# BigLatchingRelayOnAStick.net
KiCad netlist of a schematic drawn in EAGLE
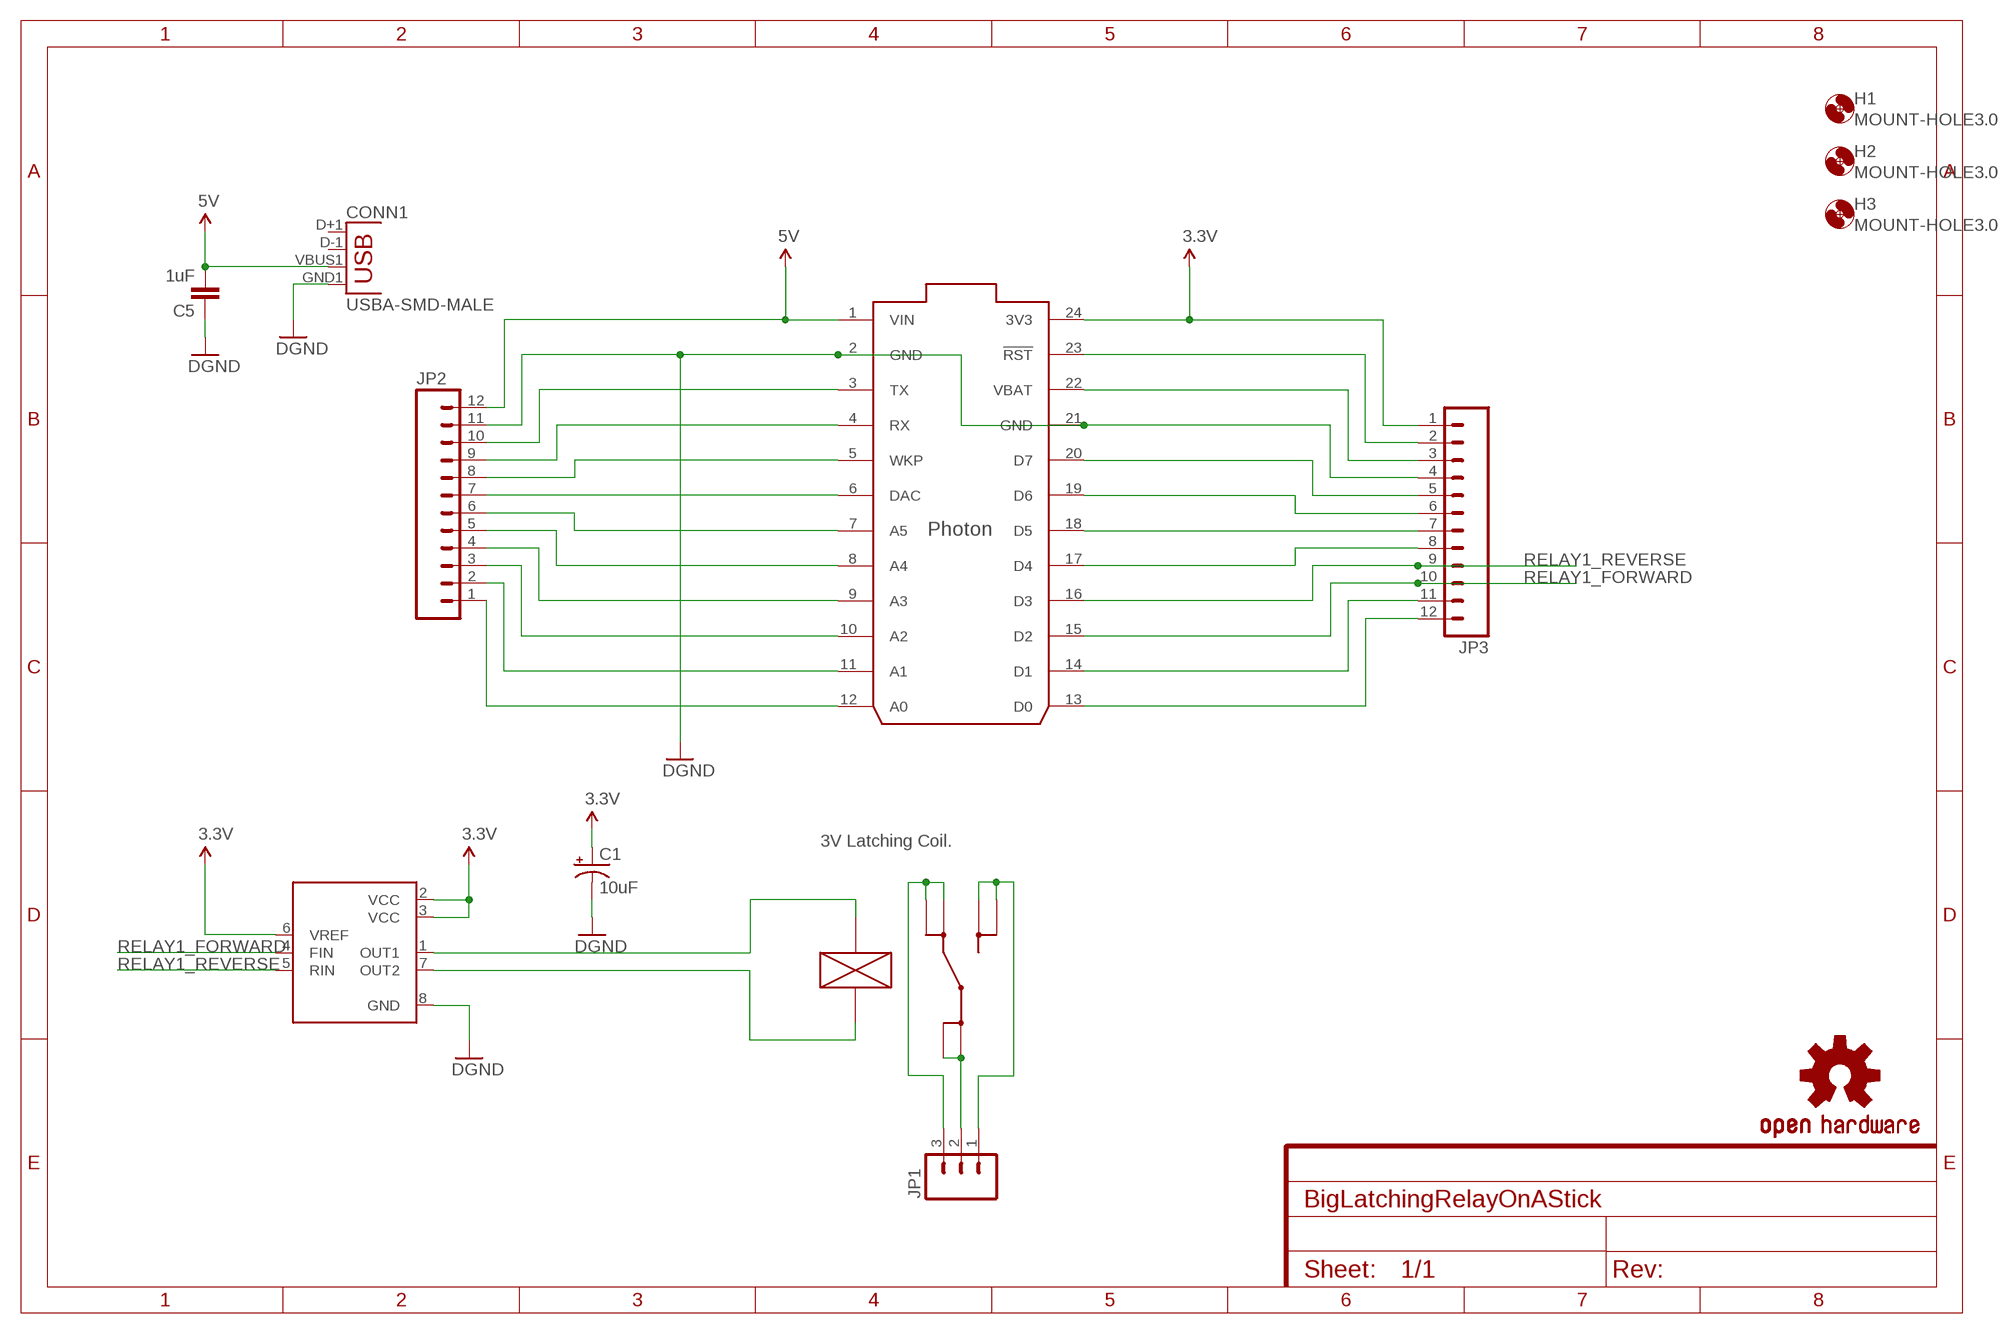
[diagram p0: schematic, sheet 1]

(export (version "E")
  (design (tool "Eeschema 10.0.6"))
  (components
    (comp (ref "C1")
      (value "10uF")
      (footprint "eagle-import:EIA3216")
      (libsource (lib "eagle-import") (part "10UF-16V-10%(TANT)"))
    )
    (comp (ref "C5")
      (value "1uF")
      (footprint "eagle-import:0805")
      (libsource (lib "eagle-import") (part "CAP0805"))
    )
    (comp (ref "CONN1")
      (value "USBA-SMD-MALE")
      (footprint "eagle-import:USB-A-SMT-MALE")
      (libsource (lib "eagle-import") (part "USBA-SMD-MALE"))
    )
    (comp (ref "H1")
      (value "MOUNT-HOLE3.0")
      (footprint "eagle-import:3,0")
      (libsource (lib "eagle-import") (part "MOUNT-HOLE3.0"))
    )
    (comp (ref "H2")
      (value "MOUNT-HOLE3.0")
      (footprint "eagle-import:3,0")
      (libsource (lib "eagle-import") (part "MOUNT-HOLE3.0"))
    )
    (comp (ref "H3")
      (value "MOUNT-HOLE3.0")
      (footprint "eagle-import:3,0")
      (libsource (lib "eagle-import") (part "MOUNT-HOLE3.0"))
    )
    (comp (ref "IC1")
      (value "PHOTON")
      (footprint "eagle-import:PHOTON")
      (libsource (lib "eagle-import") (part "PHOTON_WITH_HEADERS"))
    )
    (comp (ref "IC2")
      (value "BD6211F")
      (footprint "eagle-import:SOP8")
      (libsource (lib "eagle-import") (part "BD6211F"))
    )
    (comp (ref "JP1")
      (value "M03-SCREW-5MM")
      (footprint "eagle-import:SCREWTERMINAL-5MM-3")
      (libsource (lib "eagle-import") (part "M03-SCREW-5MM"))
    )
    (comp (ref "JP2")
      (value "M121X12_NO_SILK_KIT")
      (footprint "eagle-import:1X12_NO_SILK_KIT")
      (libsource (lib "eagle-import") (part "M121X12_NO_SILK_KIT"))
    )
    (comp (ref "JP3")
      (value "M121X12_NO_SILK_KIT")
      (footprint "eagle-import:1X12_NO_SILK_KIT")
      (libsource (lib "eagle-import") (part "M121X12_NO_SILK_KIT"))
    )
    (comp (ref "LOGO2")
      (value "OSHW-LOGOS")
      (footprint "eagle-import:OSHW-LOGO-S")
      (libsource (lib "eagle-import") (part "OSHW-LOGOS"))
    )
    (comp (ref "U$1")
      (value "RELAY_G5RL-1E")
      (footprint "eagle-import:G5RL-1E")
      (libsource (lib "eagle-import") (part "RELAY_G5RL-1E"))
    )
  )
  (nets
    (net (code "1") (name "/RELAY1_FORWARD") (class "Default")
      (node (ref "IC1") (pin "15") (pinfunction "D2_15") (pintype "bidirectional"))
      (node (ref "IC2") (pin "4") (pinfunction "FIN_4") (pintype "input"))
      (node (ref "JP3") (pin "10") (pinfunction "10_10") (pintype "passive"))
    )
    (net (code "2") (name "/RELAY1_REVERSE") (class "Default")
      (node (ref "IC1") (pin "16") (pinfunction "D3_16") (pintype "bidirectional"))
      (node (ref "IC2") (pin "5") (pinfunction "RIN_5") (pintype "input"))
      (node (ref "JP3") (pin "9") (pinfunction "9_9") (pintype "passive"))
    )
    (net (code "3") (name "3.3V") (class "Default")
      (node (ref "C1") (pin "A") (pinfunction "+_A") (pintype "passive"))
      (node (ref "IC1") (pin "24") (pinfunction "3V3_24") (pintype "power_in"))
      (node (ref "IC2") (pin "2") (pinfunction "VCC_2") (pintype "power_in"))
      (node (ref "IC2") (pin "3") (pinfunction "VCC_3") (pintype "power_in"))
      (node (ref "IC2") (pin "6") (pinfunction "VREF_6") (pintype "passive"))
      (node (ref "JP3") (pin "1") (pinfunction "1_1") (pintype "passive"))
    )
    (net (code "4") (name "5V") (class "Default")
      (node (ref "C5") (pin "2") (pinfunction "2_2") (pintype "passive"))
      (node (ref "CONN1") (pin "VBUS1") (pinfunction "VBUS_VBUS1") (pintype "bidirectional"))
      (node (ref "IC1") (pin "1") (pinfunction "VIN_1") (pintype "power_in"))
      (node (ref "JP2") (pin "12") (pinfunction "12_12") (pintype "passive"))
    )
    (net (code "5") (name "DGND") (class "Default")
      (node (ref "C1") (pin "C") (pinfunction "-_C") (pintype "passive"))
      (node (ref "C5") (pin "1") (pinfunction "1_1") (pintype "passive"))
      (node (ref "CONN1") (pin "GND1") (pinfunction "GND_GND1") (pintype "bidirectional"))
      (node (ref "IC1") (pin "2") (pinfunction "GND_2") (pintype "power_in"))
      (node (ref "IC1") (pin "21") (pinfunction "GND_21") (pintype "power_in"))
      (node (ref "IC2") (pin "8") (pinfunction "GND_8") (pintype "power_in"))
      (node (ref "JP2") (pin "11") (pinfunction "11_11") (pintype "passive"))
      (node (ref "JP3") (pin "4") (pinfunction "4_4") (pintype "passive"))
    )
    (net (code "6") (name "Net-(IC1-A0)") (class "Default")
      (node (ref "IC1") (pin "12") (pinfunction "A0_12") (pintype "bidirectional"))
      (node (ref "JP2") (pin "1") (pinfunction "1_1") (pintype "passive"))
    )
    (net (code "7") (name "Net-(IC1-A1)") (class "Default")
      (node (ref "IC1") (pin "11") (pinfunction "A1_11") (pintype "bidirectional"))
      (node (ref "JP2") (pin "2") (pinfunction "2_2") (pintype "passive"))
    )
    (net (code "8") (name "Net-(IC1-A2)") (class "Default")
      (node (ref "IC1") (pin "10") (pinfunction "A2_10") (pintype "bidirectional"))
      (node (ref "JP2") (pin "3") (pinfunction "3_3") (pintype "passive"))
    )
    (net (code "9") (name "Net-(IC1-A3)") (class "Default")
      (node (ref "IC1") (pin "9") (pinfunction "A3_9") (pintype "bidirectional"))
      (node (ref "JP2") (pin "4") (pinfunction "4_4") (pintype "passive"))
    )
    (net (code "10") (name "Net-(IC1-A4)") (class "Default")
      (node (ref "IC1") (pin "8") (pinfunction "A4_8") (pintype "bidirectional"))
      (node (ref "JP2") (pin "5") (pinfunction "5_5") (pintype "passive"))
    )
    (net (code "11") (name "Net-(IC1-A5)") (class "Default")
      (node (ref "IC1") (pin "7") (pinfunction "A5_7") (pintype "bidirectional"))
      (node (ref "JP2") (pin "6") (pinfunction "6_6") (pintype "passive"))
    )
    (net (code "12") (name "Net-(IC1-D0)") (class "Default")
      (node (ref "IC1") (pin "13") (pinfunction "D0_13") (pintype "bidirectional"))
      (node (ref "JP3") (pin "12") (pinfunction "12_12") (pintype "passive"))
    )
    (net (code "13") (name "Net-(IC1-D1)") (class "Default")
      (node (ref "IC1") (pin "14") (pinfunction "D1_14") (pintype "bidirectional"))
      (node (ref "JP3") (pin "11") (pinfunction "11_11") (pintype "passive"))
    )
    (net (code "14") (name "Net-(IC1-D4)") (class "Default")
      (node (ref "IC1") (pin "17") (pinfunction "D4_17") (pintype "bidirectional"))
      (node (ref "JP3") (pin "8") (pinfunction "8_8") (pintype "passive"))
    )
    (net (code "15") (name "Net-(IC1-D5)") (class "Default")
      (node (ref "IC1") (pin "18") (pinfunction "D5_18") (pintype "bidirectional"))
      (node (ref "JP3") (pin "7") (pinfunction "7_7") (pintype "passive"))
    )
    (net (code "16") (name "Net-(IC1-D6)") (class "Default")
      (node (ref "IC1") (pin "19") (pinfunction "D6_19") (pintype "bidirectional"))
      (node (ref "JP3") (pin "6") (pinfunction "6_6") (pintype "passive"))
    )
    (net (code "17") (name "Net-(IC1-D7)") (class "Default")
      (node (ref "IC1") (pin "20") (pinfunction "D7_20") (pintype "bidirectional"))
      (node (ref "JP3") (pin "5") (pinfunction "5_5") (pintype "passive"))
    )
    (net (code "18") (name "Net-(IC1-DAC)") (class "Default")
      (node (ref "IC1") (pin "6") (pinfunction "DAC_6") (pintype "bidirectional"))
      (node (ref "JP2") (pin "7") (pinfunction "7_7") (pintype "passive"))
    )
    (net (code "19") (name "Net-(IC1-RX)") (class "Default")
      (node (ref "IC1") (pin "4") (pinfunction "RX_4") (pintype "bidirectional"))
      (node (ref "JP2") (pin "9") (pinfunction "9_9") (pintype "passive"))
    )
    (net (code "20") (name "Net-(IC1-TX)") (class "Default")
      (node (ref "IC1") (pin "3") (pinfunction "TX_3") (pintype "bidirectional"))
      (node (ref "JP2") (pin "10") (pinfunction "10_10") (pintype "passive"))
    )
    (net (code "21") (name "Net-(IC1-VBAT)") (class "Default")
      (node (ref "IC1") (pin "22") (pinfunction "VBAT_22") (pintype "power_in"))
      (node (ref "JP3") (pin "3") (pinfunction "3_3") (pintype "passive"))
    )
    (net (code "22") (name "Net-(IC1-WKP)") (class "Default")
      (node (ref "IC1") (pin "5") (pinfunction "WKP_5") (pintype "bidirectional"))
      (node (ref "JP2") (pin "8") (pinfunction "8_8") (pintype "passive"))
    )
    (net (code "23") (name "Net-(IC1-~{RST})") (class "Default")
      (node (ref "IC1") (pin "23") (pinfunction "~{RST}_23") (pintype "bidirectional"))
      (node (ref "JP3") (pin "2") (pinfunction "2_2") (pintype "passive"))
    )
    (net (code "24") (name "Net-(IC2-OUT1)") (class "Default")
      (node (ref "IC2") (pin "1") (pinfunction "OUT1_1") (pintype "output"))
      (node (ref "U$1") (pin "COIL+") (pinfunction "COIL+_COIL+") (pintype "bidirectional"))
    )
    (net (code "25") (name "Net-(IC2-OUT2)") (class "Default")
      (node (ref "IC2") (pin "7") (pinfunction "OUT2_7") (pintype "output"))
      (node (ref "U$1") (pin "COIL-") (pinfunction "COIL-_COIL-") (pintype "bidirectional"))
    )
    (net (code "26") (name "Net-(JP1-Pad1)") (class "Default")
      (node (ref "JP1") (pin "1") (pinfunction "1_1") (pintype "passive"))
      (node (ref "U$1") (pin "NO@1") (pinfunction "NO_NO@1") (pintype "bidirectional"))
      (node (ref "U$1") (pin "NO@2") (pinfunction "NO_NO@2") (pintype "bidirectional"))
    )
    (net (code "27") (name "Net-(JP1-Pad2)") (class "Default")
      (node (ref "JP1") (pin "2") (pinfunction "2_2") (pintype "passive"))
      (node (ref "U$1") (pin "COM@1") (pinfunction "COM_COM@1") (pintype "bidirectional"))
      (node (ref "U$1") (pin "COM@2") (pinfunction "COM_COM@2") (pintype "bidirectional"))
    )
    (net (code "28") (name "Net-(JP1-Pad3)") (class "Default")
      (node (ref "JP1") (pin "3") (pinfunction "3_3") (pintype "passive"))
      (node (ref "U$1") (pin "NC@1") (pinfunction "NC_NC@1") (pintype "bidirectional"))
      (node (ref "U$1") (pin "NC@2") (pinfunction "NC_NC@2") (pintype "bidirectional"))
    )
    (net (code "29") (name "unconnected-(CONN1-D+-PadD+1)") (class "Default")
      (node (ref "CONN1") (pin "D+1") (pinfunction "D+_D+1") (pintype "bidirectional"))
    )
    (net (code "30") (name "unconnected-(CONN1-D--PadD-1)") (class "Default")
      (node (ref "CONN1") (pin "D-1") (pinfunction "D-_D-1") (pintype "bidirectional"))
    )
  )
)
